# Ad8232_placa_V2.net
KiCad netlist of a schematic drawn in EAGLE
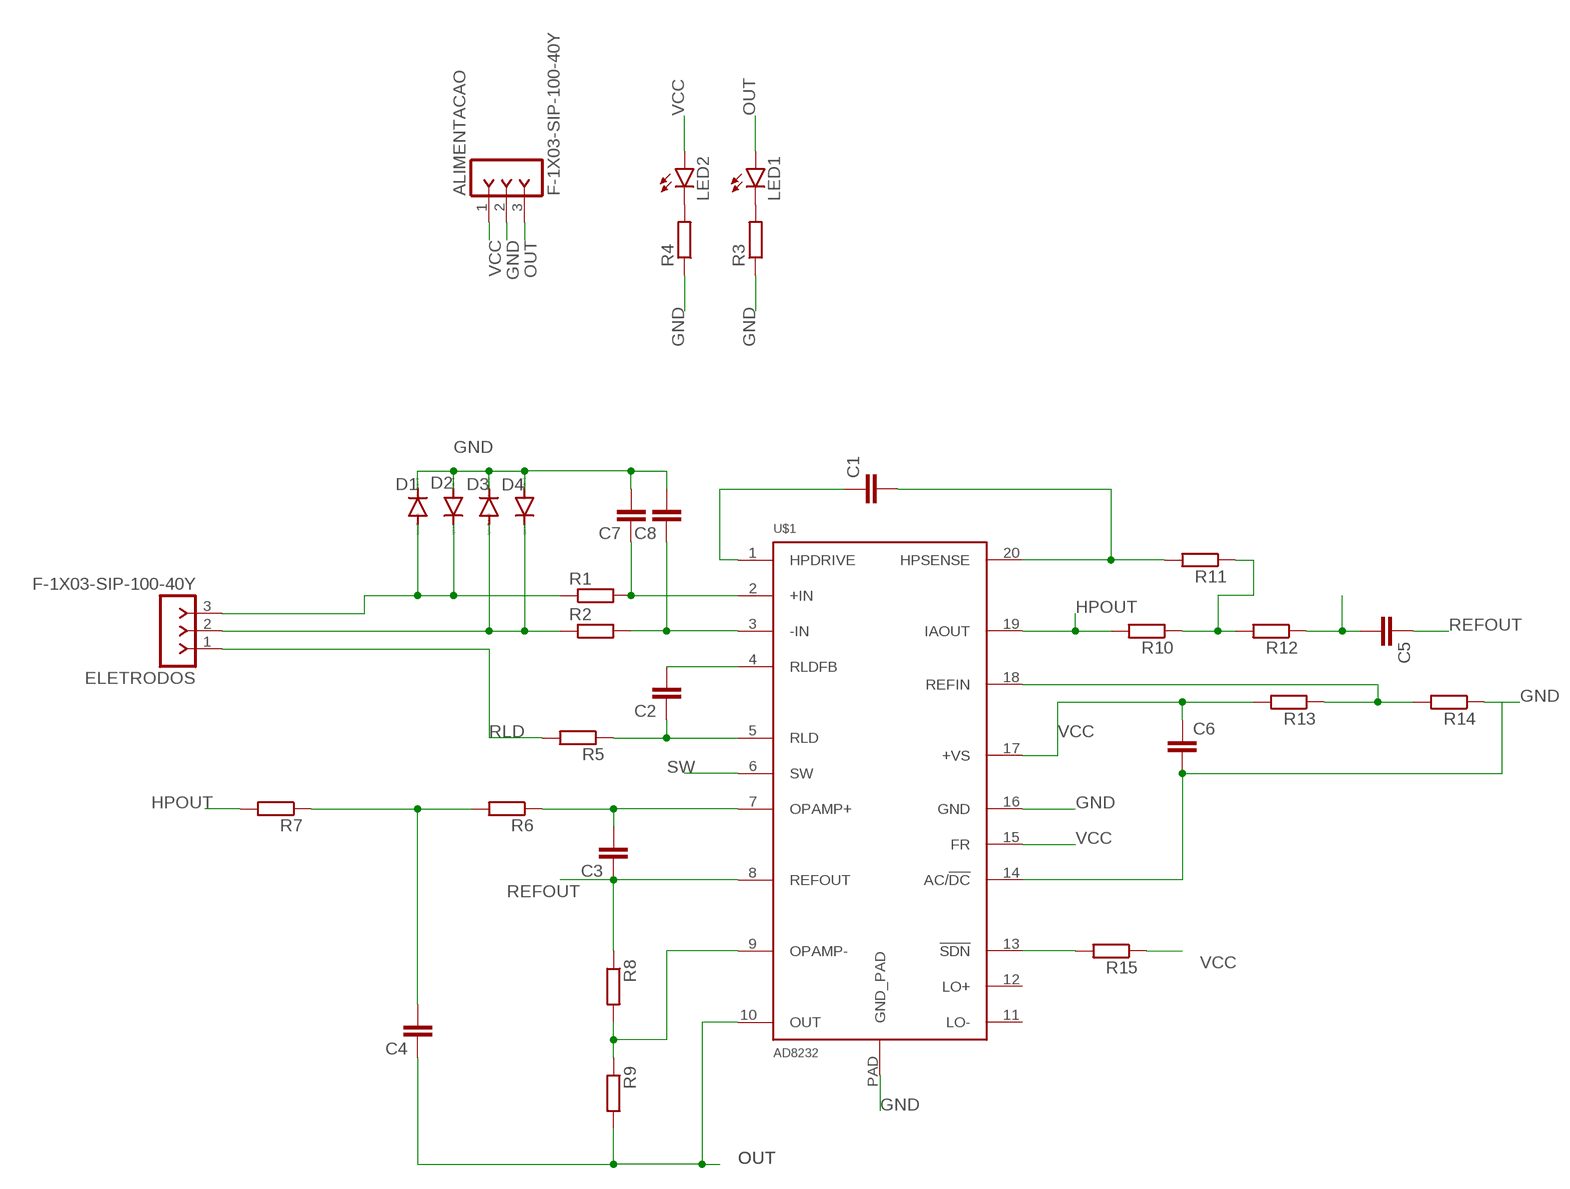
[diagram p0: schematic, sheet 1]

(export (version "E")
  (design (tool "Eeschema 10.0.6"))
  (components
    (comp (ref "ALIMENTACAO")
      (value "F-1X03-SIP-100-40Y")
      (footprint "eagle-import:SIP-100-03-40Y")
      (libsource (lib "eagle-import") (part "F-1X03-SIP-100-40Y"))
    )
    (comp (ref "C1")
      (value "C-EUC0805")
      (footprint "eagle-import:C0805")
      (libsource (lib "eagle-import") (part "C-EUC0805"))
    )
    (comp (ref "C2")
      (value "C-EUC0805")
      (footprint "eagle-import:C0805")
      (libsource (lib "eagle-import") (part "C-EUC0805"))
    )
    (comp (ref "C3")
      (value "C-EUC0805")
      (footprint "eagle-import:C0805")
      (libsource (lib "eagle-import") (part "C-EUC0805"))
    )
    (comp (ref "C4")
      (value "C-EUC0805")
      (footprint "eagle-import:C0805")
      (libsource (lib "eagle-import") (part "C-EUC0805"))
    )
    (comp (ref "C5")
      (value "C-EUC0805")
      (footprint "eagle-import:C0805")
      (libsource (lib "eagle-import") (part "C-EUC0805"))
    )
    (comp (ref "C6")
      (value "C-EUC0805")
      (footprint "eagle-import:C0805")
      (libsource (lib "eagle-import") (part "C-EUC0805"))
    )
    (comp (ref "C7")
      (value "C-EUC0805")
      (footprint "eagle-import:C0805")
      (libsource (lib "eagle-import") (part "C-EUC0805"))
    )
    (comp (ref "C8")
      (value "C-EUC0805")
      (footprint "eagle-import:C0805")
      (libsource (lib "eagle-import") (part "C-EUC0805"))
    )
    (comp (ref "D1")
      (value "DIODE-MINIMELF")
      (footprint "eagle-import:MINIMELF")
      (libsource (lib "eagle-import") (part "DIODE-MINIMELF"))
    )
    (comp (ref "D2")
      (value "DIODE-MINIMELF")
      (footprint "eagle-import:MINIMELF")
      (libsource (lib "eagle-import") (part "DIODE-MINIMELF"))
    )
    (comp (ref "D3")
      (value "DIODE-MINIMELF")
      (footprint "eagle-import:MINIMELF")
      (libsource (lib "eagle-import") (part "DIODE-MINIMELF"))
    )
    (comp (ref "D4")
      (value "DIODE-MINIMELF")
      (footprint "eagle-import:MINIMELF")
      (libsource (lib "eagle-import") (part "DIODE-MINIMELF"))
    )
    (comp (ref "ELETRODOS")
      (value "F-1X03-SIP-100-40Y")
      (footprint "eagle-import:SIP-100-03-40Y")
      (libsource (lib "eagle-import") (part "F-1X03-SIP-100-40Y"))
    )
    (comp (ref "LED1")
      (value "LEDCHIPLED_0603")
      (footprint "eagle-import:CHIPLED_0603")
      (libsource (lib "eagle-import") (part "LEDCHIPLED_0603"))
    )
    (comp (ref "LED2")
      (value "LEDCHIPLED_0603")
      (footprint "eagle-import:CHIPLED_0603")
      (libsource (lib "eagle-import") (part "LEDCHIPLED_0603"))
    )
    (comp (ref "R1")
      (value "R-EU_R0805")
      (footprint "eagle-import:R0805")
      (libsource (lib "eagle-import") (part "R-EU_R0805"))
    )
    (comp (ref "R2")
      (value "R-EU_R0805")
      (footprint "eagle-import:R0805")
      (libsource (lib "eagle-import") (part "R-EU_R0805"))
    )
    (comp (ref "R3")
      (value "R-EU_R0805")
      (footprint "eagle-import:R0805")
      (libsource (lib "eagle-import") (part "R-EU_R0805"))
    )
    (comp (ref "R4")
      (value "R-EU_R0805")
      (footprint "eagle-import:R0805")
      (libsource (lib "eagle-import") (part "R-EU_R0805"))
    )
    (comp (ref "R5")
      (value "R-EU_R0805")
      (footprint "eagle-import:R0805")
      (libsource (lib "eagle-import") (part "R-EU_R0805"))
    )
    (comp (ref "R6")
      (value "R-EU_R0805")
      (footprint "eagle-import:R0805")
      (libsource (lib "eagle-import") (part "R-EU_R0805"))
    )
    (comp (ref "R7")
      (value "R-EU_R0805")
      (footprint "eagle-import:R0805")
      (libsource (lib "eagle-import") (part "R-EU_R0805"))
    )
    (comp (ref "R8")
      (value "R-EU_R0805")
      (footprint "eagle-import:R0805")
      (libsource (lib "eagle-import") (part "R-EU_R0805"))
    )
    (comp (ref "R9")
      (value "R-EU_R0805")
      (footprint "eagle-import:R0805")
      (libsource (lib "eagle-import") (part "R-EU_R0805"))
    )
    (comp (ref "R10")
      (value "R-EU_R0805")
      (footprint "eagle-import:R0805")
      (libsource (lib "eagle-import") (part "R-EU_R0805"))
    )
    (comp (ref "R11")
      (value "R-EU_R0805")
      (footprint "eagle-import:R0805")
      (libsource (lib "eagle-import") (part "R-EU_R0805"))
    )
    (comp (ref "R12")
      (value "R-EU_R0805")
      (footprint "eagle-import:R0805")
      (libsource (lib "eagle-import") (part "R-EU_R0805"))
    )
    (comp (ref "R13")
      (value "R-EU_R0805")
      (footprint "eagle-import:R0805")
      (libsource (lib "eagle-import") (part "R-EU_R0805"))
    )
    (comp (ref "R14")
      (value "R-EU_R0805")
      (footprint "eagle-import:R0805")
      (libsource (lib "eagle-import") (part "R-EU_R0805"))
    )
    (comp (ref "R15")
      (value "R-EU_R0805")
      (footprint "eagle-import:R0805")
      (libsource (lib "eagle-import") (part "R-EU_R0805"))
    )
    (comp (ref "U$1")
      (value "AD8232")
      (footprint "eagle-import:LFCSP_20")
      (fields (field (name "MF") "Analog Devices"))
      (libsource (lib "eagle-import") (part "AD8232"))
    )
  )
  (nets
    (net (code "1") (name "/GND") (class "Default")
      (node (ref "ALIMENTACAO") (pin "2") (pinfunction "2_2") (pintype "passive"))
      (node (ref "C6") (pin "2") (pinfunction "2_2") (pintype "passive"))
      (node (ref "C7") (pin "2") (pinfunction "2_2") (pintype "passive"))
      (node (ref "C8") (pin "2") (pinfunction "2_2") (pintype "passive"))
      (node (ref "D1") (pin "C") (pinfunction "C_C") (pintype "passive"))
      (node (ref "D2") (pin "A") (pinfunction "A_A") (pintype "passive"))
      (node (ref "D3") (pin "C") (pinfunction "C_C") (pintype "passive"))
      (node (ref "D4") (pin "A") (pinfunction "A_A") (pintype "passive"))
      (node (ref "R14") (pin "1") (pinfunction "1_1") (pintype "passive"))
      (node (ref "R3") (pin "1") (pinfunction "1_1") (pintype "passive"))
      (node (ref "R4") (pin "1") (pinfunction "1_1") (pintype "passive"))
      (node (ref "U$1") (pin "14") (pinfunction "AC/~{DC}_14") (pintype "bidirectional"))
      (node (ref "U$1") (pin "16") (pinfunction "GND_16") (pintype "bidirectional"))
      (node (ref "U$1") (pin "PAD") (pinfunction "GND_PAD_PAD") (pintype "bidirectional"))
    )
    (net (code "2") (name "/HPOUT") (class "Default")
      (node (ref "R10") (pin "2") (pinfunction "2_2") (pintype "passive"))
      (node (ref "R7") (pin "2") (pinfunction "2_2") (pintype "passive"))
      (node (ref "U$1") (pin "19") (pinfunction "IAOUT_19") (pintype "bidirectional"))
    )
    (net (code "3") (name "/OUT") (class "Default")
      (node (ref "ALIMENTACAO") (pin "3") (pinfunction "3_3") (pintype "passive"))
      (node (ref "C4") (pin "1") (pinfunction "1_1") (pintype "passive"))
      (node (ref "LED1") (pin "A") (pinfunction "A_A") (pintype "passive"))
      (node (ref "R9") (pin "2") (pinfunction "2_2") (pintype "passive"))
      (node (ref "U$1") (pin "10") (pinfunction "OUT_10") (pintype "bidirectional"))
    )
    (net (code "4") (name "/REFOUT") (class "Default")
      (node (ref "C3") (pin "1") (pinfunction "1_1") (pintype "passive"))
      (node (ref "C5") (pin "1") (pinfunction "1_1") (pintype "passive"))
      (node (ref "R8") (pin "1") (pinfunction "1_1") (pintype "passive"))
      (node (ref "U$1") (pin "8") (pinfunction "REFOUT_8") (pintype "bidirectional"))
    )
    (net (code "5") (name "/RLD") (class "Default")
      (node (ref "ELETRODOS") (pin "1") (pinfunction "1_1") (pintype "passive"))
      (node (ref "R5") (pin "2") (pinfunction "2_2") (pintype "passive"))
    )
    (net (code "6") (name "/SW") (class "Default")
      (node (ref "C5") (pin "2") (pinfunction "2_2") (pintype "passive"))
      (node (ref "R12") (pin "1") (pinfunction "1_1") (pintype "passive"))
      (node (ref "U$1") (pin "6") (pinfunction "SW_6") (pintype "bidirectional"))
    )
    (net (code "7") (name "/VCC") (class "Default")
      (node (ref "ALIMENTACAO") (pin "1") (pinfunction "1_1") (pintype "passive"))
      (node (ref "C6") (pin "1") (pinfunction "1_1") (pintype "passive"))
      (node (ref "LED2") (pin "A") (pinfunction "A_A") (pintype "passive"))
      (node (ref "R13") (pin "2") (pinfunction "2_2") (pintype "passive"))
      (node (ref "R15") (pin "1") (pinfunction "1_1") (pintype "passive"))
      (node (ref "U$1") (pin "15") (pinfunction "FR_15") (pintype "bidirectional"))
      (node (ref "U$1") (pin "17") (pinfunction "+VS_17") (pintype "bidirectional"))
    )
    (net (code "8") (name "Net-(C4-Pad2)") (class "Default")
      (node (ref "C4") (pin "2") (pinfunction "2_2") (pintype "passive"))
      (node (ref "R6") (pin "2") (pinfunction "2_2") (pintype "passive"))
      (node (ref "R7") (pin "1") (pinfunction "1_1") (pintype "passive"))
    )
    (net (code "9") (name "Net-(D1-PadA)") (class "Default")
      (node (ref "D1") (pin "A") (pinfunction "A_A") (pintype "passive"))
      (node (ref "D2") (pin "C") (pinfunction "C_C") (pintype "passive"))
      (node (ref "ELETRODOS") (pin "3") (pinfunction "3_3") (pintype "passive"))
      (node (ref "R1") (pin "1") (pinfunction "1_1") (pintype "passive"))
    )
    (net (code "10") (name "Net-(D3-PadA)") (class "Default")
      (node (ref "D3") (pin "A") (pinfunction "A_A") (pintype "passive"))
      (node (ref "D4") (pin "C") (pinfunction "C_C") (pintype "passive"))
      (node (ref "ELETRODOS") (pin "2") (pinfunction "2_2") (pintype "passive"))
      (node (ref "R2") (pin "1") (pinfunction "1_1") (pintype "passive"))
    )
    (net (code "11") (name "Net-(LED1-PadC)") (class "Default")
      (node (ref "LED1") (pin "C") (pinfunction "C_C") (pintype "passive"))
      (node (ref "R3") (pin "2") (pinfunction "2_2") (pintype "passive"))
    )
    (net (code "12") (name "Net-(LED2-PadC)") (class "Default")
      (node (ref "LED2") (pin "C") (pinfunction "C_C") (pintype "passive"))
      (node (ref "R4") (pin "2") (pinfunction "2_2") (pintype "passive"))
    )
    (net (code "13") (name "Net-(R10-Pad1)") (class "Default")
      (node (ref "R10") (pin "1") (pinfunction "1_1") (pintype "passive"))
      (node (ref "R11") (pin "1") (pinfunction "1_1") (pintype "passive"))
      (node (ref "R12") (pin "2") (pinfunction "2_2") (pintype "passive"))
    )
    (net (code "14") (name "Net-(U$1-+IN)") (class "Default")
      (node (ref "C7") (pin "1") (pinfunction "1_1") (pintype "passive"))
      (node (ref "R1") (pin "2") (pinfunction "2_2") (pintype "passive"))
      (node (ref "U$1") (pin "2") (pinfunction "+IN_2") (pintype "bidirectional"))
    )
    (net (code "15") (name "Net-(U$1--IN)") (class "Default")
      (node (ref "C8") (pin "1") (pinfunction "1_1") (pintype "passive"))
      (node (ref "R2") (pin "2") (pinfunction "2_2") (pintype "passive"))
      (node (ref "U$1") (pin "3") (pinfunction "-IN_3") (pintype "bidirectional"))
    )
    (net (code "16") (name "Net-(U$1-HPDRIVE)") (class "Default")
      (node (ref "C1") (pin "1") (pinfunction "1_1") (pintype "passive"))
      (node (ref "U$1") (pin "1") (pinfunction "HPDRIVE_1") (pintype "bidirectional"))
    )
    (net (code "17") (name "Net-(U$1-HPSENSE)") (class "Default")
      (node (ref "C1") (pin "2") (pinfunction "2_2") (pintype "passive"))
      (node (ref "R11") (pin "2") (pinfunction "2_2") (pintype "passive"))
      (node (ref "U$1") (pin "20") (pinfunction "HPSENSE_20") (pintype "bidirectional"))
    )
    (net (code "18") (name "Net-(U$1-OPAMP+)") (class "Default")
      (node (ref "C3") (pin "2") (pinfunction "2_2") (pintype "passive"))
      (node (ref "R6") (pin "1") (pinfunction "1_1") (pintype "passive"))
      (node (ref "U$1") (pin "7") (pinfunction "OPAMP+_7") (pintype "bidirectional"))
    )
    (net (code "19") (name "Net-(U$1-OPAMP-)") (class "Default")
      (node (ref "R8") (pin "2") (pinfunction "2_2") (pintype "passive"))
      (node (ref "R9") (pin "1") (pinfunction "1_1") (pintype "passive"))
      (node (ref "U$1") (pin "9") (pinfunction "OPAMP-_9") (pintype "bidirectional"))
    )
    (net (code "20") (name "Net-(U$1-REFIN)") (class "Default")
      (node (ref "R13") (pin "1") (pinfunction "1_1") (pintype "passive"))
      (node (ref "R14") (pin "2") (pinfunction "2_2") (pintype "passive"))
      (node (ref "U$1") (pin "18") (pinfunction "REFIN_18") (pintype "bidirectional"))
    )
    (net (code "21") (name "Net-(U$1-RLD)") (class "Default")
      (node (ref "C2") (pin "1") (pinfunction "1_1") (pintype "passive"))
      (node (ref "R5") (pin "1") (pinfunction "1_1") (pintype "passive"))
      (node (ref "U$1") (pin "5") (pinfunction "RLD_5") (pintype "bidirectional"))
    )
    (net (code "22") (name "Net-(U$1-RLDFB)") (class "Default")
      (node (ref "C2") (pin "2") (pinfunction "2_2") (pintype "passive"))
      (node (ref "U$1") (pin "4") (pinfunction "RLDFB_4") (pintype "bidirectional"))
    )
    (net (code "23") (name "Net-(U$1-~{SDN})") (class "Default")
      (node (ref "R15") (pin "2") (pinfunction "2_2") (pintype "passive"))
      (node (ref "U$1") (pin "13") (pinfunction "~{SDN}_13") (pintype "bidirectional"))
    )
    (net (code "24") (name "unconnected-(U$1-LO+-Pad12)") (class "Default")
      (node (ref "U$1") (pin "12") (pinfunction "LO+_12") (pintype "bidirectional"))
    )
    (net (code "25") (name "unconnected-(U$1-LO--Pad11)") (class "Default")
      (node (ref "U$1") (pin "11") (pinfunction "LO-_11") (pintype "bidirectional"))
    )
  )
)
